# etapa1_anger_Y.net
KiCad netlist of a schematic drawn in Altium Designer
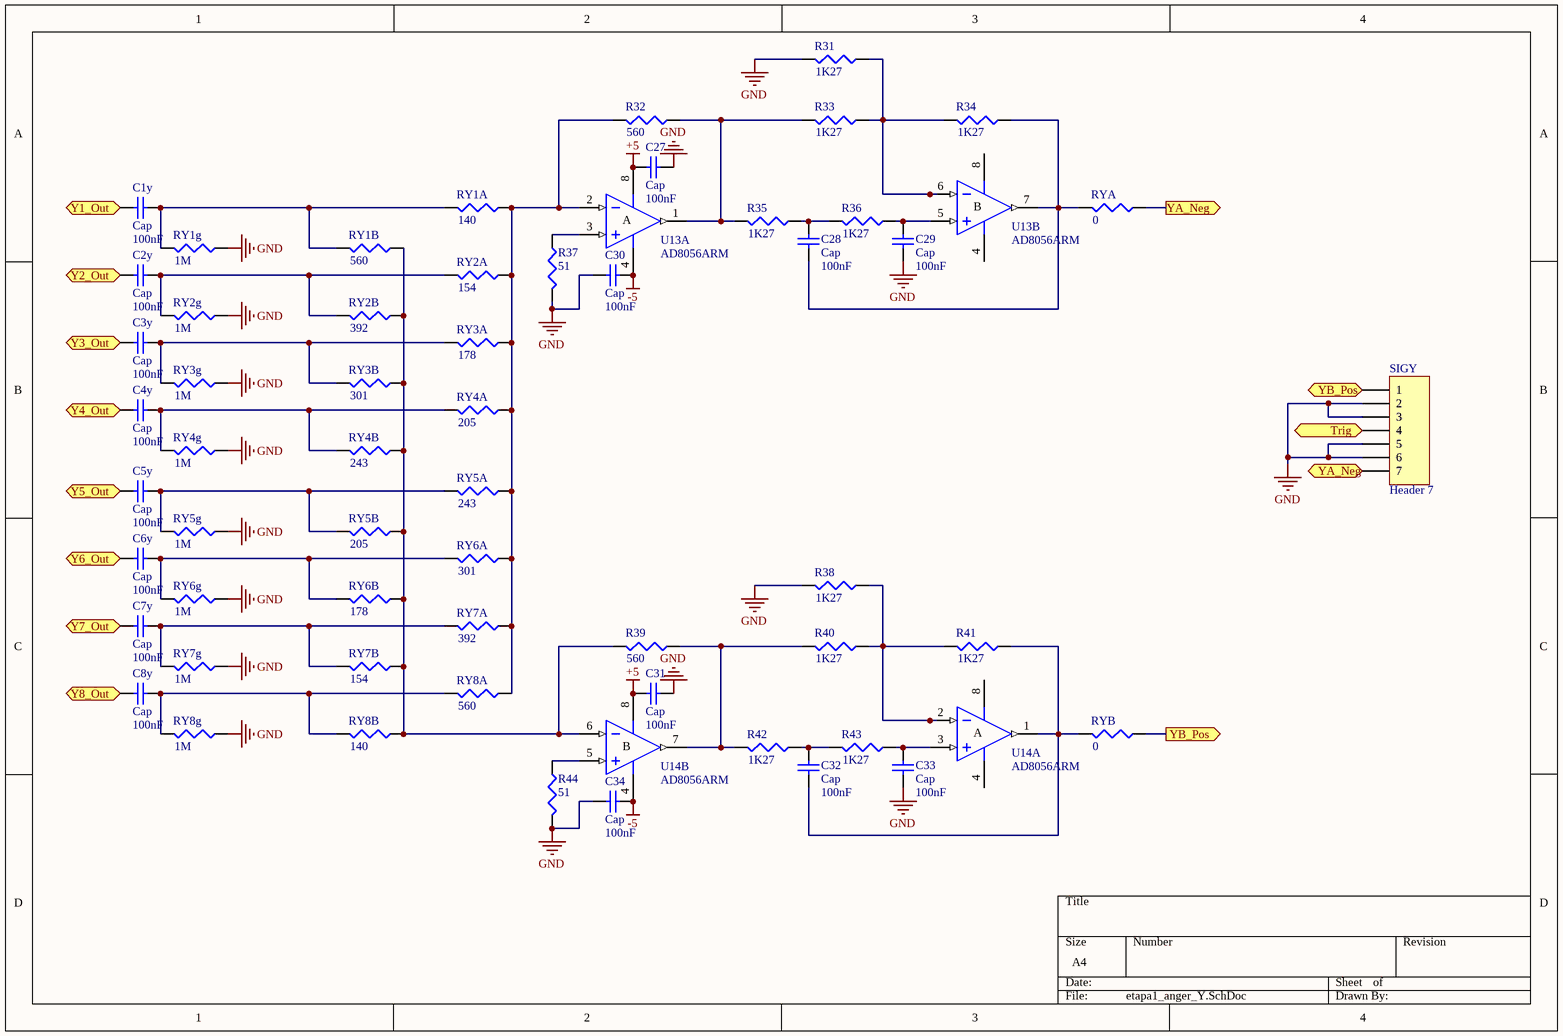
[diagram p0: etapa1_anger_Y.SchDoc]

(export (version "E")
  (design (tool "Eeschema 10.0.6"))
  (components
    (comp (ref "C1y")
      (value "Cap")
      (footprint "1608[0603]")
      (description "Capacitor")
      (fields (field (name "ALTIUM_VALUE") "100nF") (field (name "PUBLISHER") "Altium Limited"))
      (libsource (lib "Miscellaneous Devices") (part "Cap"))
    )
    (comp (ref "C2y")
      (value "Cap")
      (footprint "1608[0603]")
      (description "Capacitor")
      (fields (field (name "ALTIUM_VALUE") "100nF") (field (name "PUBLISHER") "Altium Limited"))
      (libsource (lib "Miscellaneous Devices") (part "Cap"))
    )
    (comp (ref "C3y")
      (value "Cap")
      (footprint "1608[0603]")
      (description "Capacitor")
      (fields (field (name "ALTIUM_VALUE") "100nF") (field (name "PUBLISHER") "Altium Limited"))
      (libsource (lib "Miscellaneous Devices") (part "Cap"))
    )
    (comp (ref "C4y")
      (value "Cap")
      (footprint "1608[0603]")
      (description "Capacitor")
      (fields (field (name "ALTIUM_VALUE") "100nF") (field (name "PUBLISHER") "Altium Limited"))
      (libsource (lib "Miscellaneous Devices") (part "Cap"))
    )
    (comp (ref "C5y")
      (value "Cap")
      (footprint "1608[0603]")
      (description "Capacitor")
      (fields (field (name "ALTIUM_VALUE") "100nF") (field (name "PUBLISHER") "Altium Limited"))
      (libsource (lib "Miscellaneous Devices") (part "Cap"))
    )
    (comp (ref "C6y")
      (value "Cap")
      (footprint "1608[0603]")
      (description "Capacitor")
      (fields (field (name "ALTIUM_VALUE") "100nF") (field (name "PUBLISHER") "Altium Limited"))
      (libsource (lib "Miscellaneous Devices") (part "Cap"))
    )
    (comp (ref "C7y")
      (value "Cap")
      (footprint "1608[0603]")
      (description "Capacitor")
      (fields (field (name "ALTIUM_VALUE") "100nF") (field (name "PUBLISHER") "Altium Limited"))
      (libsource (lib "Miscellaneous Devices") (part "Cap"))
    )
    (comp (ref "C8y")
      (value "Cap")
      (footprint "1608[0603]")
      (description "Capacitor")
      (fields (field (name "ALTIUM_VALUE") "100nF") (field (name "PUBLISHER") "Altium Limited"))
      (libsource (lib "Miscellaneous Devices") (part "Cap"))
    )
    (comp (ref "C27")
      (value "Cap")
      (footprint "1608[0603]")
      (description "Capacitor")
      (fields (field (name "ALTIUM_VALUE") "100nF") (field (name "PUBLISHER") "Altium Limited"))
      (libsource (lib "Miscellaneous Devices") (part "Cap"))
    )
    (comp (ref "C28")
      (value "Cap")
      (footprint "1608[0603]")
      (description "Capacitor")
      (fields (field (name "ALTIUM_VALUE") "100nF") (field (name "PUBLISHER") "Altium Limited"))
      (libsource (lib "Miscellaneous Devices") (part "Cap"))
    )
    (comp (ref "C29")
      (value "Cap")
      (footprint "1608[0603]")
      (description "Capacitor")
      (fields (field (name "ALTIUM_VALUE") "100nF") (field (name "PUBLISHER") "Altium Limited"))
      (libsource (lib "Miscellaneous Devices") (part "Cap"))
    )
    (comp (ref "C30")
      (value "Cap")
      (footprint "1608[0603]")
      (description "Capacitor")
      (fields (field (name "ALTIUM_VALUE") "100nF") (field (name "PUBLISHER") "Altium Limited"))
      (libsource (lib "Miscellaneous Devices") (part "Cap"))
    )
    (comp (ref "C31")
      (value "Cap")
      (footprint "1608[0603]")
      (description "Capacitor")
      (fields (field (name "ALTIUM_VALUE") "100nF") (field (name "PUBLISHER") "Altium Limited"))
      (libsource (lib "Miscellaneous Devices") (part "Cap"))
    )
    (comp (ref "C32")
      (value "Cap")
      (footprint "1608[0603]")
      (description "Capacitor")
      (fields (field (name "ALTIUM_VALUE") "100nF") (field (name "PUBLISHER") "Altium Limited"))
      (libsource (lib "Miscellaneous Devices") (part "Cap"))
    )
    (comp (ref "C33")
      (value "Cap")
      (footprint "1608[0603]")
      (description "Capacitor")
      (fields (field (name "ALTIUM_VALUE") "100nF") (field (name "PUBLISHER") "Altium Limited"))
      (libsource (lib "Miscellaneous Devices") (part "Cap"))
    )
    (comp (ref "C34")
      (value "Cap")
      (footprint "1608[0603]")
      (description "Capacitor")
      (fields (field (name "ALTIUM_VALUE") "100nF") (field (name "PUBLISHER") "Altium Limited"))
      (libsource (lib "Miscellaneous Devices") (part "Cap"))
    )
    (comp (ref "R31")
      (value "1K27")
      (footprint "1608[0603]")
      (description "Resistor")
      (fields (field (name "Comment") "Res3") (field (name "PUBLISHER") "Altium Limited"))
      (libsource (lib "Miscellaneous Devices") (part "Res3"))
    )
    (comp (ref "R32")
      (value "560")
      (footprint "0402")
      (description "Resistor")
      (fields (field (name "Comment") "Res3") (field (name "PUBLISHER") "Altium Limited"))
      (libsource (lib "Miscellaneous Devices") (part "Res3"))
    )
    (comp (ref "R33")
      (value "1K27")
      (footprint "0402")
      (description "Resistor")
      (fields (field (name "Comment") "Res3") (field (name "PUBLISHER") "Altium Limited"))
      (libsource (lib "Miscellaneous Devices") (part "Res3"))
    )
    (comp (ref "R34")
      (value "1K27")
      (footprint "0402")
      (description "Resistor")
      (fields (field (name "Comment") "Res3") (field (name "PUBLISHER") "Altium Limited"))
      (libsource (lib "Miscellaneous Devices") (part "Res3"))
    )
    (comp (ref "R35")
      (value "1K27")
      (footprint "0402")
      (description "Resistor")
      (fields (field (name "Comment") "Res3") (field (name "PUBLISHER") "Altium Limited"))
      (libsource (lib "Miscellaneous Devices") (part "Res3"))
    )
    (comp (ref "R36")
      (value "1K27")
      (footprint "0402")
      (description "Resistor")
      (fields (field (name "Comment") "Res3") (field (name "PUBLISHER") "Altium Limited"))
      (libsource (lib "Miscellaneous Devices") (part "Res3"))
    )
    (comp (ref "R37")
      (value "51")
      (footprint "0402")
      (description "Resistor")
      (fields (field (name "Comment") "Res3") (field (name "PUBLISHER") "Altium Limited"))
      (libsource (lib "Miscellaneous Devices") (part "Res3"))
    )
    (comp (ref "R38")
      (value "1K27")
      (footprint "1608[0603]")
      (description "Resistor")
      (fields (field (name "Comment") "Res3") (field (name "PUBLISHER") "Altium Limited"))
      (libsource (lib "Miscellaneous Devices") (part "Res3"))
    )
    (comp (ref "R39")
      (value "560")
      (footprint "0402")
      (description "Resistor")
      (fields (field (name "Comment") "Res3") (field (name "PUBLISHER") "Altium Limited"))
      (libsource (lib "Miscellaneous Devices") (part "Res3"))
    )
    (comp (ref "R40")
      (value "1K27")
      (footprint "0402")
      (description "Resistor")
      (fields (field (name "Comment") "Res3") (field (name "PUBLISHER") "Altium Limited"))
      (libsource (lib "Miscellaneous Devices") (part "Res3"))
    )
    (comp (ref "R41")
      (value "1K27")
      (footprint "0402")
      (description "Resistor")
      (fields (field (name "Comment") "Res3") (field (name "PUBLISHER") "Altium Limited"))
      (libsource (lib "Miscellaneous Devices") (part "Res3"))
    )
    (comp (ref "R42")
      (value "1K27")
      (footprint "0402")
      (description "Resistor")
      (fields (field (name "Comment") "Res3") (field (name "PUBLISHER") "Altium Limited"))
      (libsource (lib "Miscellaneous Devices") (part "Res3"))
    )
    (comp (ref "R43")
      (value "1K27")
      (footprint "0402")
      (description "Resistor")
      (fields (field (name "Comment") "Res3") (field (name "PUBLISHER") "Altium Limited"))
      (libsource (lib "Miscellaneous Devices") (part "Res3"))
    )
    (comp (ref "R44")
      (value "51")
      (footprint "0402")
      (description "Resistor")
      (fields (field (name "Comment") "Res3") (field (name "PUBLISHER") "Altium Limited"))
      (libsource (lib "Miscellaneous Devices") (part "Res3"))
    )
    (comp (ref "RY1A")
      (value "140")
      (footprint "0402")
      (description "Resistor")
      (fields (field (name "Comment") "Res3") (field (name "PUBLISHER") "Altium Limited"))
      (libsource (lib "Miscellaneous Devices") (part "Res3"))
    )
    (comp (ref "RY1B")
      (value "560")
      (footprint "0402")
      (description "Resistor")
      (fields (field (name "Comment") "Res3") (field (name "PUBLISHER") "Altium Limited"))
      (libsource (lib "Miscellaneous Devices") (part "Res3"))
    )
    (comp (ref "RY1g")
      (value "1M")
      (footprint "J1-0603")
      (description "Resistor")
      (fields (field (name "Comment") "Res3") (field (name "PUBLISHER") "Altium Limited"))
      (libsource (lib "Miscellaneous Devices") (part "Res3"))
    )
    (comp (ref "RY2A")
      (value "154")
      (footprint "0402")
      (description "Resistor")
      (fields (field (name "Comment") "Res3") (field (name "PUBLISHER") "Altium Limited"))
      (libsource (lib "Miscellaneous Devices") (part "Res3"))
    )
    (comp (ref "RY2B")
      (value "392")
      (footprint "0402")
      (description "Resistor")
      (fields (field (name "Comment") "Res3") (field (name "PUBLISHER") "Altium Limited"))
      (libsource (lib "Miscellaneous Devices") (part "Res3"))
    )
    (comp (ref "RY2g")
      (value "1M")
      (footprint "J1-0603")
      (description "Resistor")
      (fields (field (name "Comment") "Res3") (field (name "PUBLISHER") "Altium Limited"))
      (libsource (lib "Miscellaneous Devices") (part "Res3"))
    )
    (comp (ref "RY3A")
      (value "178")
      (footprint "0402")
      (description "Resistor")
      (fields (field (name "Comment") "Res3") (field (name "PUBLISHER") "Altium Limited"))
      (libsource (lib "Miscellaneous Devices") (part "Res3"))
    )
    (comp (ref "RY3B")
      (value "301")
      (footprint "0402")
      (description "Resistor")
      (fields (field (name "Comment") "Res3") (field (name "PUBLISHER") "Altium Limited"))
      (libsource (lib "Miscellaneous Devices") (part "Res3"))
    )
    (comp (ref "RY3g")
      (value "1M")
      (footprint "J1-0603")
      (description "Resistor")
      (fields (field (name "Comment") "Res3") (field (name "PUBLISHER") "Altium Limited"))
      (libsource (lib "Miscellaneous Devices") (part "Res3"))
    )
    (comp (ref "RY4A")
      (value "205")
      (footprint "0402")
      (description "Resistor")
      (fields (field (name "Comment") "Res3") (field (name "PUBLISHER") "Altium Limited"))
      (libsource (lib "Miscellaneous Devices") (part "Res3"))
    )
    (comp (ref "RY4B")
      (value "243")
      (footprint "0402")
      (description "Resistor")
      (fields (field (name "Comment") "Res3") (field (name "PUBLISHER") "Altium Limited"))
      (libsource (lib "Miscellaneous Devices") (part "Res3"))
    )
    (comp (ref "RY4g")
      (value "1M")
      (footprint "J1-0603")
      (description "Resistor")
      (fields (field (name "Comment") "Res3") (field (name "PUBLISHER") "Altium Limited"))
      (libsource (lib "Miscellaneous Devices") (part "Res3"))
    )
    (comp (ref "RY5A")
      (value "243")
      (footprint "0402")
      (description "Resistor")
      (fields (field (name "Comment") "Res3") (field (name "PUBLISHER") "Altium Limited"))
      (libsource (lib "Miscellaneous Devices") (part "Res3"))
    )
    (comp (ref "RY5B")
      (value "205")
      (footprint "0402")
      (description "Resistor")
      (fields (field (name "Comment") "Res3") (field (name "PUBLISHER") "Altium Limited"))
      (libsource (lib "Miscellaneous Devices") (part "Res3"))
    )
    (comp (ref "RY5g")
      (value "1M")
      (footprint "J1-0603")
      (description "Resistor")
      (fields (field (name "Comment") "Res3") (field (name "PUBLISHER") "Altium Limited"))
      (libsource (lib "Miscellaneous Devices") (part "Res3"))
    )
    (comp (ref "RY6A")
      (value "301")
      (footprint "0402")
      (description "Resistor")
      (fields (field (name "Comment") "Res3") (field (name "PUBLISHER") "Altium Limited"))
      (libsource (lib "Miscellaneous Devices") (part "Res3"))
    )
    (comp (ref "RY6B")
      (value "178")
      (footprint "0402")
      (description "Resistor")
      (fields (field (name "Comment") "Res3") (field (name "PUBLISHER") "Altium Limited"))
      (libsource (lib "Miscellaneous Devices") (part "Res3"))
    )
    (comp (ref "RY6g")
      (value "1M")
      (footprint "J1-0603")
      (description "Resistor")
      (fields (field (name "Comment") "Res3") (field (name "PUBLISHER") "Altium Limited"))
      (libsource (lib "Miscellaneous Devices") (part "Res3"))
    )
    (comp (ref "RY7A")
      (value "392")
      (footprint "0402")
      (description "Resistor")
      (fields (field (name "Comment") "Res3") (field (name "PUBLISHER") "Altium Limited"))
      (libsource (lib "Miscellaneous Devices") (part "Res3"))
    )
    (comp (ref "RY7B")
      (value "154")
      (footprint "0402")
      (description "Resistor")
      (fields (field (name "Comment") "Res3") (field (name "PUBLISHER") "Altium Limited"))
      (libsource (lib "Miscellaneous Devices") (part "Res3"))
    )
    (comp (ref "RY7g")
      (value "1M")
      (footprint "J1-0603")
      (description "Resistor")
      (fields (field (name "Comment") "Res3") (field (name "PUBLISHER") "Altium Limited"))
      (libsource (lib "Miscellaneous Devices") (part "Res3"))
    )
    (comp (ref "RY8A")
      (value "560")
      (footprint "0402")
      (description "Resistor")
      (fields (field (name "Comment") "Res3") (field (name "PUBLISHER") "Altium Limited"))
      (libsource (lib "Miscellaneous Devices") (part "Res3"))
    )
    (comp (ref "RY8B")
      (value "140")
      (footprint "0402")
      (description "Resistor")
      (fields (field (name "Comment") "Res3") (field (name "PUBLISHER") "Altium Limited"))
      (libsource (lib "Miscellaneous Devices") (part "Res3"))
    )
    (comp (ref "RY8g")
      (value "1M")
      (footprint "J1-0603")
      (description "Resistor")
      (fields (field (name "Comment") "Res3") (field (name "PUBLISHER") "Altium Limited"))
      (libsource (lib "Miscellaneous Devices") (part "Res3"))
    )
    (comp (ref "RYA")
      (value "0")
      (footprint "0402")
      (description "Resistor")
      (fields (field (name "Comment") "Res3") (field (name "PUBLISHER") "Altium Limited"))
      (libsource (lib "Miscellaneous Devices") (part "Res3"))
    )
    (comp (ref "RYB")
      (value "0")
      (footprint "0402")
      (description "Resistor")
      (fields (field (name "Comment") "Res3") (field (name "PUBLISHER") "Altium Limited"))
      (libsource (lib "Miscellaneous Devices") (part "Res3"))
    )
    (comp (ref "SIGY")
      (value "Header 7")
      (footprint "HDR1X7")
      (description "Header, 7-Pin")
      (fields (field (name "PUBLISHER") "Altium Limited"))
      (libsource (lib "Miscellaneous Connectors") (part "Header 7"))
    )
    (comp (ref "U13")
      (value "AD8056ARM")
      (footprint "RM-8")
      (description "Low Cost, 300MHz Voltage Feedback Amplifier")
      (fields (field (name "PUBLISHER") "Altium Limited"))
      (libsource (lib "AD Operational Amplifier") (part "AD8056ARM"))
    )
    (comp (ref "U14")
      (value "AD8056ARM")
      (footprint "RM-8")
      (description "Low Cost, 300MHz Voltage Feedback Amplifier")
      (fields (field (name "PUBLISHER") "Altium Limited"))
      (libsource (lib "AD Operational Amplifier") (part "AD8056ARM"))
    )
  )
  (nets
    (net (code "1") (name "+5") (class "Default")
      (node (ref "C27") (pin "1") (pinfunction "1_1") (pintype "passive"))
      (node (ref "C31") (pin "1") (pinfunction "1_1") (pintype "passive"))
      (node (ref "U13") (pin "8") (pinfunction "V+_8") (pintype "power_in"))
      (node (ref "U14") (pin "8") (pinfunction "V+_8") (pintype "power_in"))
    )
    (net (code "2") (name "-5") (class "Default")
      (node (ref "C30") (pin "2") (pinfunction "2_2") (pintype "passive"))
      (node (ref "C34") (pin "2") (pinfunction "2_2") (pintype "passive"))
      (node (ref "U13") (pin "4") (pinfunction "V-_4") (pintype "power_in"))
      (node (ref "U14") (pin "4") (pinfunction "V-_4") (pintype "power_in"))
    )
    (net (code "3") (name "/Trig") (class "Default")
      (node (ref "SIGY") (pin "4") (pinfunction "4_4") (pintype "passive"))
    )
    (net (code "4") (name "/Y1_Out") (class "Default")
      (node (ref "C1y") (pin "1") (pinfunction "1_1") (pintype "passive"))
    )
    (net (code "5") (name "/Y2_Out") (class "Default")
      (node (ref "C2y") (pin "1") (pinfunction "1_1") (pintype "passive"))
    )
    (net (code "6") (name "/Y3_Out") (class "Default")
      (node (ref "C3y") (pin "1") (pinfunction "1_1") (pintype "passive"))
    )
    (net (code "7") (name "/Y4_Out") (class "Default")
      (node (ref "C4y") (pin "1") (pinfunction "1_1") (pintype "passive"))
    )
    (net (code "8") (name "/Y5_Out") (class "Default")
      (node (ref "C5y") (pin "1") (pinfunction "1_1") (pintype "passive"))
    )
    (net (code "9") (name "/Y6_Out") (class "Default")
      (node (ref "C6y") (pin "1") (pinfunction "1_1") (pintype "passive"))
    )
    (net (code "10") (name "/Y7_Out") (class "Default")
      (node (ref "C7y") (pin "1") (pinfunction "1_1") (pintype "passive"))
    )
    (net (code "11") (name "/Y8_Out") (class "Default")
      (node (ref "C8y") (pin "1") (pinfunction "1_1") (pintype "passive"))
    )
    (net (code "12") (name "/YA_Neg") (class "Default")
      (node (ref "RYA") (pin "1") (pinfunction "1_1") (pintype "passive"))
      (node (ref "SIGY") (pin "7") (pinfunction "7_7") (pintype "passive"))
    )
    (net (code "13") (name "/YB_Pos") (class "Default")
      (node (ref "RYB") (pin "1") (pinfunction "1_1") (pintype "passive"))
      (node (ref "SIGY") (pin "1") (pinfunction "1_1") (pintype "passive"))
    )
    (net (code "14") (name "GND") (class "Default")
      (node (ref "C27") (pin "2") (pinfunction "2_2") (pintype "passive"))
      (node (ref "C29") (pin "2") (pinfunction "2_2") (pintype "passive"))
      (node (ref "C30") (pin "1") (pinfunction "1_1") (pintype "passive"))
      (node (ref "C31") (pin "2") (pinfunction "2_2") (pintype "passive"))
      (node (ref "C33") (pin "2") (pinfunction "2_2") (pintype "passive"))
      (node (ref "C34") (pin "1") (pinfunction "1_1") (pintype "passive"))
      (node (ref "R31") (pin "2") (pinfunction "2_2") (pintype "passive"))
      (node (ref "R37") (pin "2") (pinfunction "2_2") (pintype "passive"))
      (node (ref "R38") (pin "2") (pinfunction "2_2") (pintype "passive"))
      (node (ref "R44") (pin "2") (pinfunction "2_2") (pintype "passive"))
      (node (ref "RY1g") (pin "1") (pinfunction "1_1") (pintype "passive"))
      (node (ref "RY2g") (pin "1") (pinfunction "1_1") (pintype "passive"))
      (node (ref "RY3g") (pin "1") (pinfunction "1_1") (pintype "passive"))
      (node (ref "RY4g") (pin "1") (pinfunction "1_1") (pintype "passive"))
      (node (ref "RY5g") (pin "1") (pinfunction "1_1") (pintype "passive"))
      (node (ref "RY6g") (pin "1") (pinfunction "1_1") (pintype "passive"))
      (node (ref "RY7g") (pin "1") (pinfunction "1_1") (pintype "passive"))
      (node (ref "RY8g") (pin "1") (pinfunction "1_1") (pintype "passive"))
      (node (ref "SIGY") (pin "2") (pinfunction "2_2") (pintype "passive"))
      (node (ref "SIGY") (pin "3") (pinfunction "3_3") (pintype "passive"))
      (node (ref "SIGY") (pin "5") (pinfunction "5_5") (pintype "passive"))
      (node (ref "SIGY") (pin "6") (pinfunction "6_6") (pintype "passive"))
    )
    (net (code "15") (name "Net-(C1y-Pad2)") (class "Default")
      (node (ref "C1y") (pin "2") (pinfunction "2_2") (pintype "passive"))
      (node (ref "RY1A") (pin "2") (pinfunction "2_2") (pintype "passive"))
      (node (ref "RY1B") (pin "2") (pinfunction "2_2") (pintype "passive"))
      (node (ref "RY1g") (pin "2") (pinfunction "2_2") (pintype "passive"))
    )
    (net (code "16") (name "Net-(C2y-Pad2)") (class "Default")
      (node (ref "C2y") (pin "2") (pinfunction "2_2") (pintype "passive"))
      (node (ref "RY2A") (pin "2") (pinfunction "2_2") (pintype "passive"))
      (node (ref "RY2B") (pin "2") (pinfunction "2_2") (pintype "passive"))
      (node (ref "RY2g") (pin "2") (pinfunction "2_2") (pintype "passive"))
    )
    (net (code "17") (name "Net-(C3y-Pad2)") (class "Default")
      (node (ref "C3y") (pin "2") (pinfunction "2_2") (pintype "passive"))
      (node (ref "RY3A") (pin "2") (pinfunction "2_2") (pintype "passive"))
      (node (ref "RY3B") (pin "2") (pinfunction "2_2") (pintype "passive"))
      (node (ref "RY3g") (pin "2") (pinfunction "2_2") (pintype "passive"))
    )
    (net (code "18") (name "Net-(C4y-Pad2)") (class "Default")
      (node (ref "C4y") (pin "2") (pinfunction "2_2") (pintype "passive"))
      (node (ref "RY4A") (pin "2") (pinfunction "2_2") (pintype "passive"))
      (node (ref "RY4B") (pin "2") (pinfunction "2_2") (pintype "passive"))
      (node (ref "RY4g") (pin "2") (pinfunction "2_2") (pintype "passive"))
    )
    (net (code "19") (name "Net-(C5y-Pad2)") (class "Default")
      (node (ref "C5y") (pin "2") (pinfunction "2_2") (pintype "passive"))
      (node (ref "RY5A") (pin "2") (pinfunction "2_2") (pintype "passive"))
      (node (ref "RY5B") (pin "2") (pinfunction "2_2") (pintype "passive"))
      (node (ref "RY5g") (pin "2") (pinfunction "2_2") (pintype "passive"))
    )
    (net (code "20") (name "Net-(C6y-Pad2)") (class "Default")
      (node (ref "C6y") (pin "2") (pinfunction "2_2") (pintype "passive"))
      (node (ref "RY6A") (pin "2") (pinfunction "2_2") (pintype "passive"))
      (node (ref "RY6B") (pin "2") (pinfunction "2_2") (pintype "passive"))
      (node (ref "RY6g") (pin "2") (pinfunction "2_2") (pintype "passive"))
    )
    (net (code "21") (name "Net-(C7y-Pad2)") (class "Default")
      (node (ref "C7y") (pin "2") (pinfunction "2_2") (pintype "passive"))
      (node (ref "RY7A") (pin "2") (pinfunction "2_2") (pintype "passive"))
      (node (ref "RY7B") (pin "2") (pinfunction "2_2") (pintype "passive"))
      (node (ref "RY7g") (pin "2") (pinfunction "2_2") (pintype "passive"))
    )
    (net (code "22") (name "Net-(C8y-Pad2)") (class "Default")
      (node (ref "C8y") (pin "2") (pinfunction "2_2") (pintype "passive"))
      (node (ref "RY8A") (pin "2") (pinfunction "2_2") (pintype "passive"))
      (node (ref "RY8B") (pin "2") (pinfunction "2_2") (pintype "passive"))
      (node (ref "RY8g") (pin "2") (pinfunction "2_2") (pintype "passive"))
    )
    (net (code "23") (name "Net-(C28-Pad1)") (class "Default")
      (node (ref "C28") (pin "1") (pinfunction "1_1") (pintype "passive"))
      (node (ref "R35") (pin "1") (pinfunction "1_1") (pintype "passive"))
      (node (ref "R36") (pin "2") (pinfunction "2_2") (pintype "passive"))
    )
    (net (code "24") (name "Net-(C32-Pad1)") (class "Default")
      (node (ref "C32") (pin "1") (pinfunction "1_1") (pintype "passive"))
      (node (ref "R42") (pin "1") (pinfunction "1_1") (pintype "passive"))
      (node (ref "R43") (pin "2") (pinfunction "2_2") (pintype "passive"))
    )
    (net (code "25") (name "Net-(U13A-IN+)") (class "Default")
      (node (ref "R37") (pin "1") (pinfunction "1_1") (pintype "passive"))
      (node (ref "U13") (pin "3") (pinfunction "IN+_3") (pintype "input"))
    )
    (net (code "26") (name "Net-(U13A-IN-)") (class "Default")
      (node (ref "R32") (pin "2") (pinfunction "2_2") (pintype "passive"))
      (node (ref "RY1A") (pin "1") (pinfunction "1_1") (pintype "passive"))
      (node (ref "RY2A") (pin "1") (pinfunction "1_1") (pintype "passive"))
      (node (ref "RY3A") (pin "1") (pinfunction "1_1") (pintype "passive"))
      (node (ref "RY4A") (pin "1") (pinfunction "1_1") (pintype "passive"))
      (node (ref "RY5A") (pin "1") (pinfunction "1_1") (pintype "passive"))
      (node (ref "RY6A") (pin "1") (pinfunction "1_1") (pintype "passive"))
      (node (ref "RY7A") (pin "1") (pinfunction "1_1") (pintype "passive"))
      (node (ref "RY8A") (pin "1") (pinfunction "1_1") (pintype "passive"))
      (node (ref "U13") (pin "2") (pinfunction "IN-_2") (pintype "input"))
    )
    (net (code "27") (name "Net-(U13A-OUT)") (class "Default")
      (node (ref "R32") (pin "1") (pinfunction "1_1") (pintype "passive"))
      (node (ref "R33") (pin "2") (pinfunction "2_2") (pintype "passive"))
      (node (ref "R35") (pin "2") (pinfunction "2_2") (pintype "passive"))
      (node (ref "U13") (pin "1") (pinfunction "OUT_1") (pintype "output"))
    )
    (net (code "28") (name "Net-(U13B-IN+)") (class "Default")
      (node (ref "C29") (pin "1") (pinfunction "1_1") (pintype "passive"))
      (node (ref "R36") (pin "1") (pinfunction "1_1") (pintype "passive"))
      (node (ref "U13") (pin "5") (pinfunction "IN+_5") (pintype "input"))
    )
    (net (code "29") (name "Net-(U13B-IN-)") (class "Default")
      (node (ref "R31") (pin "1") (pinfunction "1_1") (pintype "passive"))
      (node (ref "R33") (pin "1") (pinfunction "1_1") (pintype "passive"))
      (node (ref "R34") (pin "2") (pinfunction "2_2") (pintype "passive"))
      (node (ref "U13") (pin "6") (pinfunction "IN-_6") (pintype "input"))
    )
    (net (code "30") (name "Net-(U13B-OUT)") (class "Default")
      (node (ref "C28") (pin "2") (pinfunction "2_2") (pintype "passive"))
      (node (ref "R34") (pin "1") (pinfunction "1_1") (pintype "passive"))
      (node (ref "RYA") (pin "2") (pinfunction "2_2") (pintype "passive"))
      (node (ref "U13") (pin "7") (pinfunction "OUT_7") (pintype "output"))
    )
    (net (code "31") (name "Net-(U14A-IN+)") (class "Default")
      (node (ref "C33") (pin "1") (pinfunction "1_1") (pintype "passive"))
      (node (ref "R43") (pin "1") (pinfunction "1_1") (pintype "passive"))
      (node (ref "U14") (pin "3") (pinfunction "IN+_3") (pintype "input"))
    )
    (net (code "32") (name "Net-(U14A-IN-)") (class "Default")
      (node (ref "R38") (pin "1") (pinfunction "1_1") (pintype "passive"))
      (node (ref "R40") (pin "1") (pinfunction "1_1") (pintype "passive"))
      (node (ref "R41") (pin "2") (pinfunction "2_2") (pintype "passive"))
      (node (ref "U14") (pin "2") (pinfunction "IN-_2") (pintype "input"))
    )
    (net (code "33") (name "Net-(U14A-OUT)") (class "Default")
      (node (ref "C32") (pin "2") (pinfunction "2_2") (pintype "passive"))
      (node (ref "R41") (pin "1") (pinfunction "1_1") (pintype "passive"))
      (node (ref "RYB") (pin "2") (pinfunction "2_2") (pintype "passive"))
      (node (ref "U14") (pin "1") (pinfunction "OUT_1") (pintype "output"))
    )
    (net (code "34") (name "Net-(U14B-IN+)") (class "Default")
      (node (ref "R44") (pin "1") (pinfunction "1_1") (pintype "passive"))
      (node (ref "U14") (pin "5") (pinfunction "IN+_5") (pintype "input"))
    )
    (net (code "35") (name "Net-(U14B-IN-)") (class "Default")
      (node (ref "R39") (pin "2") (pinfunction "2_2") (pintype "passive"))
      (node (ref "RY1B") (pin "1") (pinfunction "1_1") (pintype "passive"))
      (node (ref "RY2B") (pin "1") (pinfunction "1_1") (pintype "passive"))
      (node (ref "RY3B") (pin "1") (pinfunction "1_1") (pintype "passive"))
      (node (ref "RY4B") (pin "1") (pinfunction "1_1") (pintype "passive"))
      (node (ref "RY5B") (pin "1") (pinfunction "1_1") (pintype "passive"))
      (node (ref "RY6B") (pin "1") (pinfunction "1_1") (pintype "passive"))
      (node (ref "RY7B") (pin "1") (pinfunction "1_1") (pintype "passive"))
      (node (ref "RY8B") (pin "1") (pinfunction "1_1") (pintype "passive"))
      (node (ref "U14") (pin "6") (pinfunction "IN-_6") (pintype "input"))
    )
    (net (code "36") (name "Net-(U14B-OUT)") (class "Default")
      (node (ref "R39") (pin "1") (pinfunction "1_1") (pintype "passive"))
      (node (ref "R40") (pin "2") (pinfunction "2_2") (pintype "passive"))
      (node (ref "R42") (pin "2") (pinfunction "2_2") (pintype "passive"))
      (node (ref "U14") (pin "7") (pinfunction "OUT_7") (pintype "output"))
    )
    (net (code "37") (name "unconnected-(U13B-V+-Pad8)") (class "Default")
      (node (ref "U13") (pin "8") (pinfunction "V+_8") (pintype "power_in"))
    )
    (net (code "38") (name "unconnected-(U13B-V--Pad4)") (class "Default")
      (node (ref "U13") (pin "4") (pinfunction "V-_4") (pintype "power_in"))
    )
    (net (code "39") (name "unconnected-(U14A-V+-Pad8)") (class "Default")
      (node (ref "U14") (pin "8") (pinfunction "V+_8") (pintype "power_in"))
    )
    (net (code "40") (name "unconnected-(U14A-V--Pad4)") (class "Default")
      (node (ref "U14") (pin "4") (pinfunction "V-_4") (pintype "power_in"))
    )
  )
)
